# FLEX_TOP_MOSFETS.net
KiCad netlist of a schematic drawn in Altium Designer
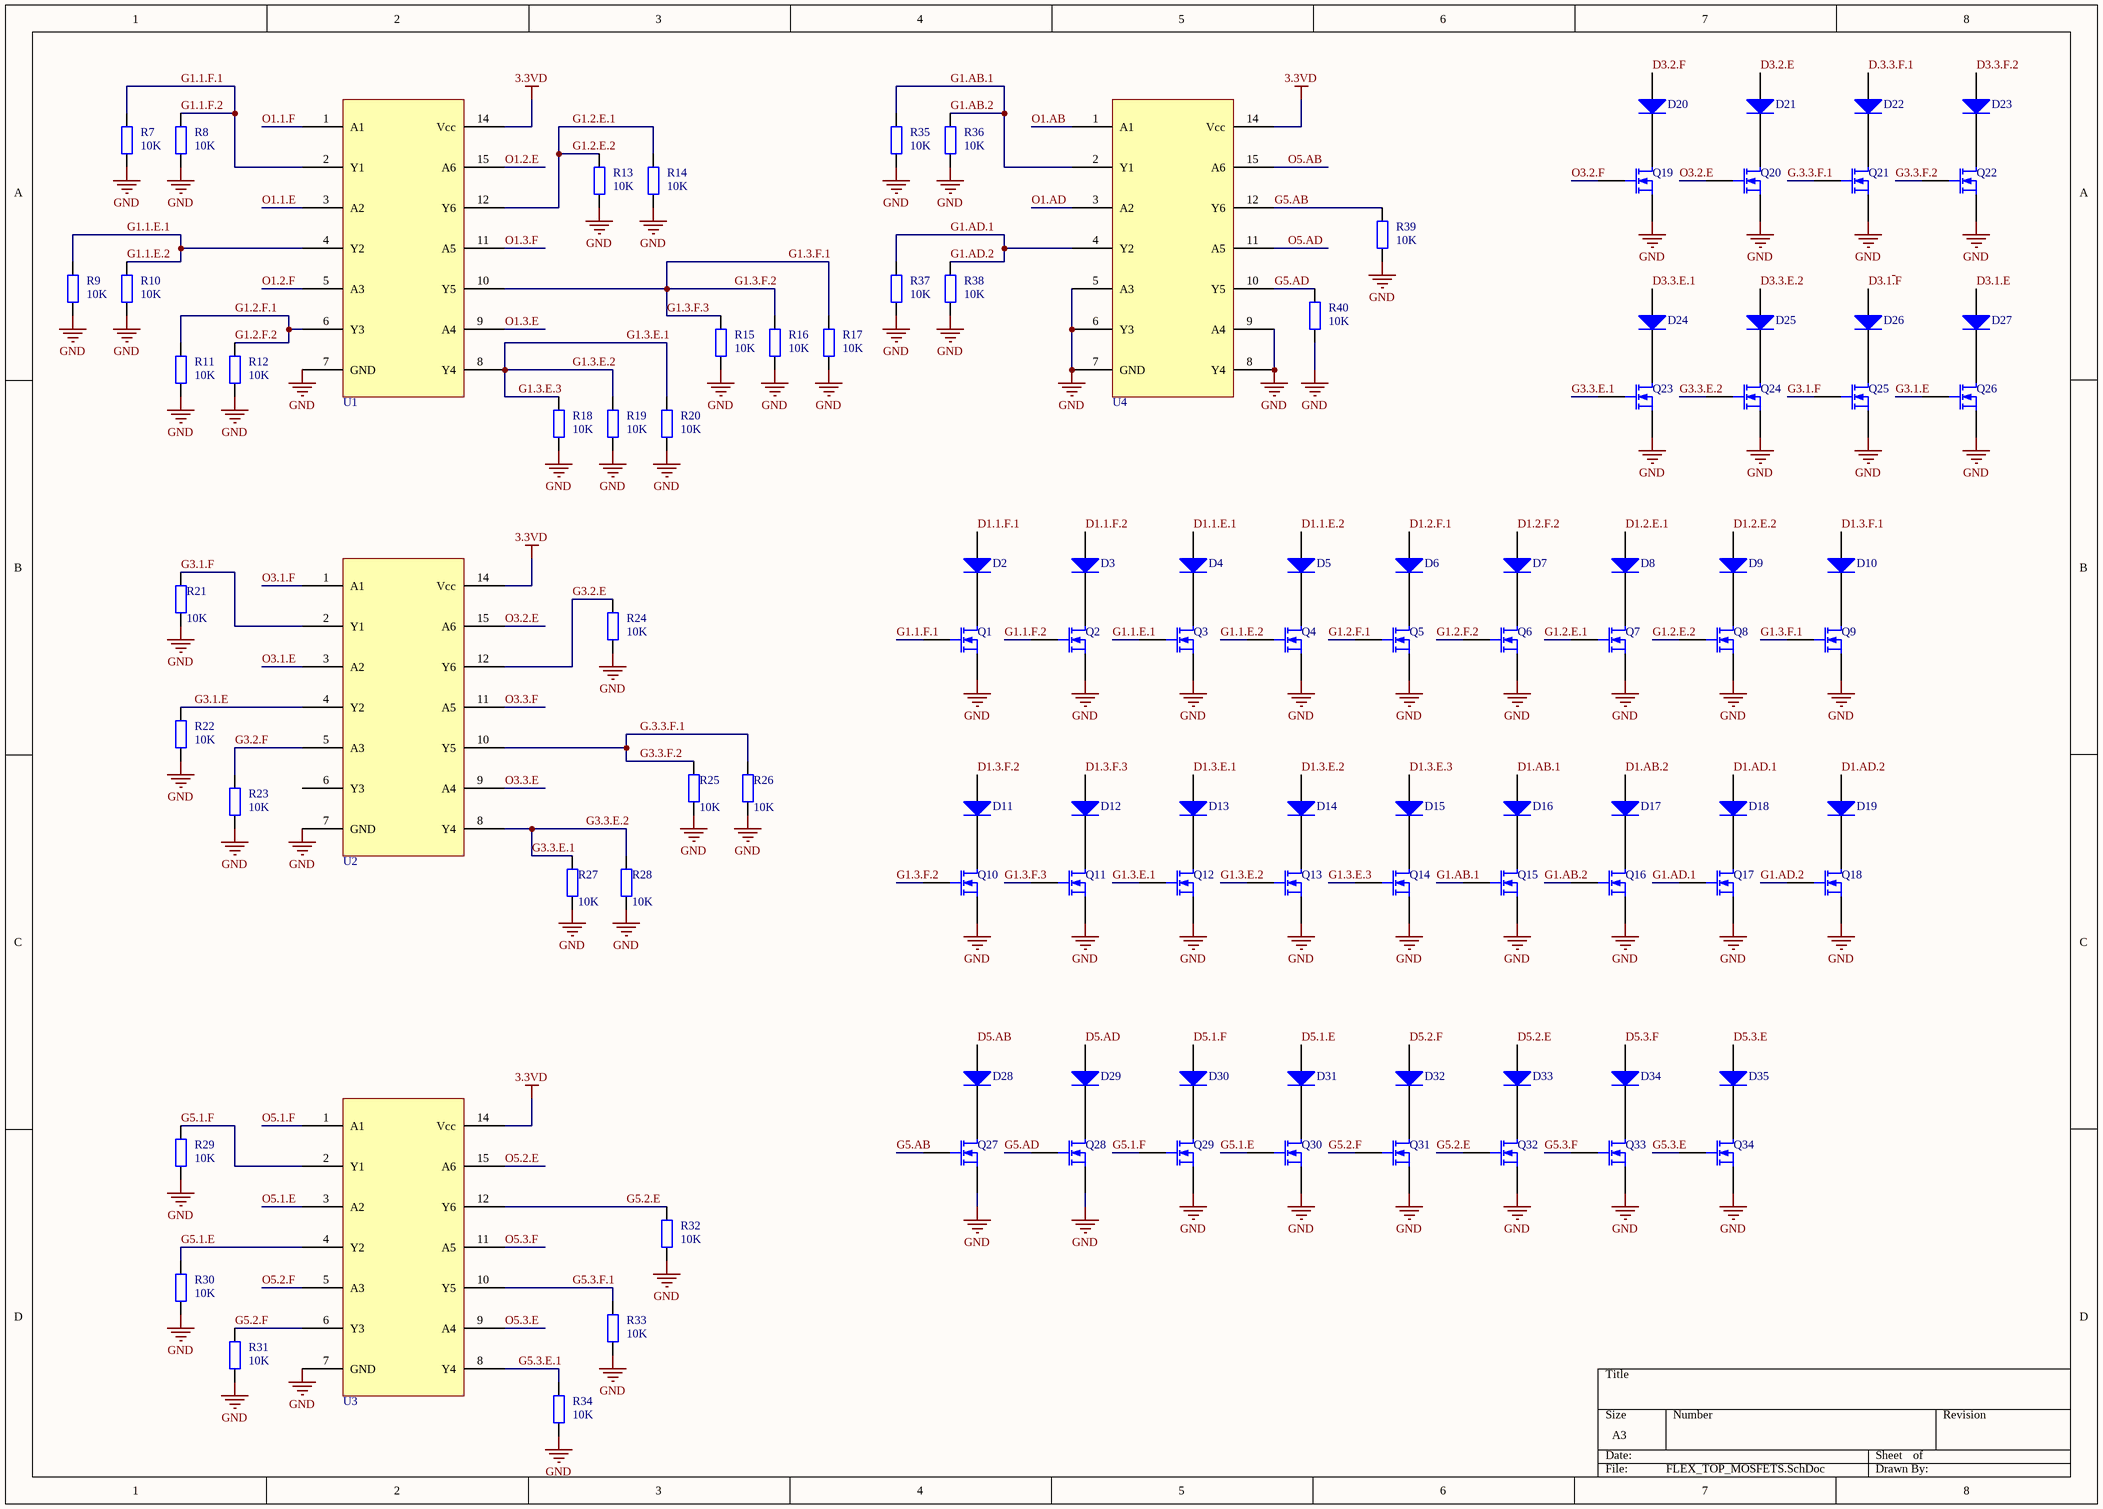
[diagram p0: FLEX_TOP_MOSFETS.SchDoc]

(export (version "E")
  (design (tool "Eeschema 10.0.6"))
  (components
    (comp (ref "D2")
      (value "de")
      (footprint "Diode_Shottky")
      (description "Default Diode")
      (fields (field (name "PUBLISHER") "Altium Limited"))
      (libsource (lib "Miscellaneous Devices") (part "Diode"))
    )
    (comp (ref "D3")
      (value "de")
      (footprint "Diode_Shottky")
      (description "Default Diode")
      (fields (field (name "PUBLISHER") "Altium Limited"))
      (libsource (lib "Miscellaneous Devices") (part "Diode"))
    )
    (comp (ref "D4")
      (value "de")
      (footprint "Diode_Shottky")
      (description "Default Diode")
      (fields (field (name "PUBLISHER") "Altium Limited"))
      (libsource (lib "Miscellaneous Devices") (part "Diode"))
    )
    (comp (ref "D5")
      (value "de")
      (footprint "Diode_Shottky")
      (description "Default Diode")
      (fields (field (name "PUBLISHER") "Altium Limited"))
      (libsource (lib "Miscellaneous Devices") (part "Diode"))
    )
    (comp (ref "D6")
      (value "de")
      (footprint "Diode_Shottky")
      (description "Default Diode")
      (fields (field (name "PUBLISHER") "Altium Limited"))
      (libsource (lib "Miscellaneous Devices") (part "Diode"))
    )
    (comp (ref "D7")
      (value "de")
      (footprint "Diode_Shottky")
      (description "Default Diode")
      (fields (field (name "PUBLISHER") "Altium Limited"))
      (libsource (lib "Miscellaneous Devices") (part "Diode"))
    )
    (comp (ref "D8")
      (value "de")
      (footprint "Diode_Shottky")
      (description "Default Diode")
      (fields (field (name "PUBLISHER") "Altium Limited"))
      (libsource (lib "Miscellaneous Devices") (part "Diode"))
    )
    (comp (ref "D9")
      (value "de")
      (footprint "Diode_Shottky")
      (description "Default Diode")
      (fields (field (name "PUBLISHER") "Altium Limited"))
      (libsource (lib "Miscellaneous Devices") (part "Diode"))
    )
    (comp (ref "D10")
      (value "de")
      (footprint "Diode_Shottky")
      (description "Default Diode")
      (fields (field (name "PUBLISHER") "Altium Limited"))
      (libsource (lib "Miscellaneous Devices") (part "Diode"))
    )
    (comp (ref "D11")
      (value "de")
      (footprint "Diode_Shottky")
      (description "Default Diode")
      (fields (field (name "PUBLISHER") "Altium Limited"))
      (libsource (lib "Miscellaneous Devices") (part "Diode"))
    )
    (comp (ref "D12")
      (value "de")
      (footprint "Diode_Shottky")
      (description "Default Diode")
      (fields (field (name "PUBLISHER") "Altium Limited"))
      (libsource (lib "Miscellaneous Devices") (part "Diode"))
    )
    (comp (ref "D13")
      (value "de")
      (footprint "Diode_Shottky")
      (description "Default Diode")
      (fields (field (name "PUBLISHER") "Altium Limited"))
      (libsource (lib "Miscellaneous Devices") (part "Diode"))
    )
    (comp (ref "D14")
      (value "de")
      (footprint "Diode_Shottky")
      (description "Default Diode")
      (fields (field (name "PUBLISHER") "Altium Limited"))
      (libsource (lib "Miscellaneous Devices") (part "Diode"))
    )
    (comp (ref "D15")
      (value "de")
      (footprint "Diode_Shottky")
      (description "Default Diode")
      (fields (field (name "PUBLISHER") "Altium Limited"))
      (libsource (lib "Miscellaneous Devices") (part "Diode"))
    )
    (comp (ref "D16")
      (value "de")
      (footprint "Diode_Shottky")
      (description "Default Diode")
      (fields (field (name "PUBLISHER") "Altium Limited"))
      (libsource (lib "Miscellaneous Devices") (part "Diode"))
    )
    (comp (ref "D17")
      (value "de")
      (footprint "Diode_Shottky")
      (description "Default Diode")
      (fields (field (name "PUBLISHER") "Altium Limited"))
      (libsource (lib "Miscellaneous Devices") (part "Diode"))
    )
    (comp (ref "D18")
      (value "de")
      (footprint "Diode_Shottky")
      (description "Default Diode")
      (fields (field (name "PUBLISHER") "Altium Limited"))
      (libsource (lib "Miscellaneous Devices") (part "Diode"))
    )
    (comp (ref "D19")
      (value "de")
      (footprint "Diode_Shottky")
      (description "Default Diode")
      (fields (field (name "PUBLISHER") "Altium Limited"))
      (libsource (lib "Miscellaneous Devices") (part "Diode"))
    )
    (comp (ref "D20")
      (value "de")
      (footprint "Diode_Shottky")
      (description "Default Diode")
      (fields (field (name "PUBLISHER") "Altium Limited"))
      (libsource (lib "Miscellaneous Devices") (part "Diode"))
    )
    (comp (ref "D21")
      (value "de")
      (footprint "Diode_Shottky")
      (description "Default Diode")
      (fields (field (name "PUBLISHER") "Altium Limited"))
      (libsource (lib "Miscellaneous Devices") (part "Diode"))
    )
    (comp (ref "D22")
      (value "de")
      (footprint "Diode_Shottky")
      (description "Default Diode")
      (fields (field (name "PUBLISHER") "Altium Limited"))
      (libsource (lib "Miscellaneous Devices") (part "Diode"))
    )
    (comp (ref "D23")
      (value "de")
      (footprint "Diode_Shottky")
      (description "Default Diode")
      (fields (field (name "PUBLISHER") "Altium Limited"))
      (libsource (lib "Miscellaneous Devices") (part "Diode"))
    )
    (comp (ref "D24")
      (value "de")
      (footprint "Diode_Shottky")
      (description "Default Diode")
      (fields (field (name "PUBLISHER") "Altium Limited"))
      (libsource (lib "Miscellaneous Devices") (part "Diode"))
    )
    (comp (ref "D25")
      (value "de")
      (footprint "Diode_Shottky")
      (description "Default Diode")
      (fields (field (name "PUBLISHER") "Altium Limited"))
      (libsource (lib "Miscellaneous Devices") (part "Diode"))
    )
    (comp (ref "D26")
      (value "de")
      (footprint "Diode_Shottky")
      (description "Default Diode")
      (fields (field (name "PUBLISHER") "Altium Limited"))
      (libsource (lib "Miscellaneous Devices") (part "Diode"))
    )
    (comp (ref "D27")
      (value "de")
      (footprint "Diode_Shottky")
      (description "Default Diode")
      (fields (field (name "PUBLISHER") "Altium Limited"))
      (libsource (lib "Miscellaneous Devices") (part "Diode"))
    )
    (comp (ref "D28")
      (value "de")
      (footprint "Diode_Shottky")
      (description "Default Diode")
      (fields (field (name "PUBLISHER") "Altium Limited"))
      (libsource (lib "Miscellaneous Devices") (part "Diode"))
    )
    (comp (ref "D29")
      (value "de")
      (footprint "Diode_Shottky")
      (description "Default Diode")
      (fields (field (name "PUBLISHER") "Altium Limited"))
      (libsource (lib "Miscellaneous Devices") (part "Diode"))
    )
    (comp (ref "D30")
      (value "de")
      (footprint "Diode_Shottky")
      (description "Default Diode")
      (fields (field (name "PUBLISHER") "Altium Limited"))
      (libsource (lib "Miscellaneous Devices") (part "Diode"))
    )
    (comp (ref "D31")
      (value "de")
      (footprint "Diode_Shottky")
      (description "Default Diode")
      (fields (field (name "PUBLISHER") "Altium Limited"))
      (libsource (lib "Miscellaneous Devices") (part "Diode"))
    )
    (comp (ref "D32")
      (value "de")
      (footprint "Diode_Shottky")
      (description "Default Diode")
      (fields (field (name "PUBLISHER") "Altium Limited"))
      (libsource (lib "Miscellaneous Devices") (part "Diode"))
    )
    (comp (ref "D33")
      (value "de")
      (footprint "Diode_Shottky")
      (description "Default Diode")
      (fields (field (name "PUBLISHER") "Altium Limited"))
      (libsource (lib "Miscellaneous Devices") (part "Diode"))
    )
    (comp (ref "D34")
      (value "de")
      (footprint "Diode_Shottky")
      (description "Default Diode")
      (fields (field (name "PUBLISHER") "Altium Limited"))
      (libsource (lib "Miscellaneous Devices") (part "Diode"))
    )
    (comp (ref "D35")
      (value "de")
      (footprint "Diode_Shottky")
      (description "Default Diode")
      (fields (field (name "PUBLISHER") "Altium Limited"))
      (libsource (lib "Miscellaneous Devices") (part "Diode"))
    )
    (comp (ref "Q1")
      (value "~")
      (footprint "MOSFET")
      (description "N-Channel MOSFET")
      (fields (field (name "PUBLISHER") "Altium Limited"))
      (libsource (lib "Miscellaneous Devices") (part "MOSFET-N"))
    )
    (comp (ref "Q2")
      (value "~")
      (footprint "MOSFET")
      (description "N-Channel MOSFET")
      (fields (field (name "PUBLISHER") "Altium Limited"))
      (libsource (lib "Miscellaneous Devices") (part "MOSFET-N"))
    )
    (comp (ref "Q3")
      (value "~")
      (footprint "MOSFET")
      (description "N-Channel MOSFET")
      (fields (field (name "PUBLISHER") "Altium Limited"))
      (libsource (lib "Miscellaneous Devices") (part "MOSFET-N"))
    )
    (comp (ref "Q4")
      (value "~")
      (footprint "MOSFET")
      (description "N-Channel MOSFET")
      (fields (field (name "PUBLISHER") "Altium Limited"))
      (libsource (lib "Miscellaneous Devices") (part "MOSFET-N"))
    )
    (comp (ref "Q5")
      (value "~")
      (footprint "MOSFET")
      (description "N-Channel MOSFET")
      (fields (field (name "PUBLISHER") "Altium Limited"))
      (libsource (lib "Miscellaneous Devices") (part "MOSFET-N"))
    )
    (comp (ref "Q6")
      (value "~")
      (footprint "MOSFET")
      (description "N-Channel MOSFET")
      (fields (field (name "PUBLISHER") "Altium Limited"))
      (libsource (lib "Miscellaneous Devices") (part "MOSFET-N"))
    )
    (comp (ref "Q7")
      (value "~")
      (footprint "MOSFET")
      (description "N-Channel MOSFET")
      (fields (field (name "PUBLISHER") "Altium Limited"))
      (libsource (lib "Miscellaneous Devices") (part "MOSFET-N"))
    )
    (comp (ref "Q8")
      (value "~")
      (footprint "MOSFET")
      (description "N-Channel MOSFET")
      (fields (field (name "PUBLISHER") "Altium Limited"))
      (libsource (lib "Miscellaneous Devices") (part "MOSFET-N"))
    )
    (comp (ref "Q9")
      (value "~")
      (footprint "MOSFET")
      (description "N-Channel MOSFET")
      (fields (field (name "PUBLISHER") "Altium Limited"))
      (libsource (lib "Miscellaneous Devices") (part "MOSFET-N"))
    )
    (comp (ref "Q10")
      (value "~")
      (footprint "MOSFET")
      (description "N-Channel MOSFET")
      (fields (field (name "PUBLISHER") "Altium Limited"))
      (libsource (lib "Miscellaneous Devices") (part "MOSFET-N"))
    )
    (comp (ref "Q11")
      (value "~")
      (footprint "MOSFET")
      (description "N-Channel MOSFET")
      (fields (field (name "PUBLISHER") "Altium Limited"))
      (libsource (lib "Miscellaneous Devices") (part "MOSFET-N"))
    )
    (comp (ref "Q12")
      (value "~")
      (footprint "MOSFET")
      (description "N-Channel MOSFET")
      (fields (field (name "PUBLISHER") "Altium Limited"))
      (libsource (lib "Miscellaneous Devices") (part "MOSFET-N"))
    )
    (comp (ref "Q13")
      (value "~")
      (footprint "MOSFET")
      (description "N-Channel MOSFET")
      (fields (field (name "PUBLISHER") "Altium Limited"))
      (libsource (lib "Miscellaneous Devices") (part "MOSFET-N"))
    )
    (comp (ref "Q14")
      (value "~")
      (footprint "MOSFET")
      (description "N-Channel MOSFET")
      (fields (field (name "PUBLISHER") "Altium Limited"))
      (libsource (lib "Miscellaneous Devices") (part "MOSFET-N"))
    )
    (comp (ref "Q15")
      (value "~")
      (footprint "MOSFET")
      (description "N-Channel MOSFET")
      (fields (field (name "PUBLISHER") "Altium Limited"))
      (libsource (lib "Miscellaneous Devices") (part "MOSFET-N"))
    )
    (comp (ref "Q16")
      (value "~")
      (footprint "MOSFET")
      (description "N-Channel MOSFET")
      (fields (field (name "PUBLISHER") "Altium Limited"))
      (libsource (lib "Miscellaneous Devices") (part "MOSFET-N"))
    )
    (comp (ref "Q17")
      (value "~")
      (footprint "MOSFET")
      (description "N-Channel MOSFET")
      (fields (field (name "PUBLISHER") "Altium Limited"))
      (libsource (lib "Miscellaneous Devices") (part "MOSFET-N"))
    )
    (comp (ref "Q18")
      (value "~")
      (footprint "MOSFET")
      (description "N-Channel MOSFET")
      (fields (field (name "PUBLISHER") "Altium Limited"))
      (libsource (lib "Miscellaneous Devices") (part "MOSFET-N"))
    )
    (comp (ref "Q19")
      (value "~")
      (footprint "MOSFET")
      (description "N-Channel MOSFET")
      (fields (field (name "PUBLISHER") "Altium Limited"))
      (libsource (lib "Miscellaneous Devices") (part "MOSFET-N"))
    )
    (comp (ref "Q20")
      (value "~")
      (footprint "MOSFET")
      (description "N-Channel MOSFET")
      (fields (field (name "PUBLISHER") "Altium Limited"))
      (libsource (lib "Miscellaneous Devices") (part "MOSFET-N"))
    )
    (comp (ref "Q21")
      (value "~")
      (footprint "MOSFET")
      (description "N-Channel MOSFET")
      (fields (field (name "PUBLISHER") "Altium Limited"))
      (libsource (lib "Miscellaneous Devices") (part "MOSFET-N"))
    )
    (comp (ref "Q22")
      (value "~")
      (footprint "MOSFET")
      (description "N-Channel MOSFET")
      (fields (field (name "PUBLISHER") "Altium Limited"))
      (libsource (lib "Miscellaneous Devices") (part "MOSFET-N"))
    )
    (comp (ref "Q23")
      (value "~")
      (footprint "MOSFET")
      (description "N-Channel MOSFET")
      (fields (field (name "PUBLISHER") "Altium Limited"))
      (libsource (lib "Miscellaneous Devices") (part "MOSFET-N"))
    )
    (comp (ref "Q24")
      (value "~")
      (footprint "MOSFET")
      (description "N-Channel MOSFET")
      (fields (field (name "PUBLISHER") "Altium Limited"))
      (libsource (lib "Miscellaneous Devices") (part "MOSFET-N"))
    )
    (comp (ref "Q25")
      (value "~")
      (footprint "MOSFET")
      (description "N-Channel MOSFET")
      (fields (field (name "PUBLISHER") "Altium Limited"))
      (libsource (lib "Miscellaneous Devices") (part "MOSFET-N"))
    )
    (comp (ref "Q26")
      (value "~")
      (footprint "MOSFET")
      (description "N-Channel MOSFET")
      (fields (field (name "PUBLISHER") "Altium Limited"))
      (libsource (lib "Miscellaneous Devices") (part "MOSFET-N"))
    )
    (comp (ref "Q27")
      (value "~")
      (footprint "MOSFET")
      (description "N-Channel MOSFET")
      (fields (field (name "PUBLISHER") "Altium Limited"))
      (libsource (lib "Miscellaneous Devices") (part "MOSFET-N"))
    )
    (comp (ref "Q28")
      (value "~")
      (footprint "MOSFET")
      (description "N-Channel MOSFET")
      (fields (field (name "PUBLISHER") "Altium Limited"))
      (libsource (lib "Miscellaneous Devices") (part "MOSFET-N"))
    )
    (comp (ref "Q29")
      (value "~")
      (footprint "MOSFET")
      (description "N-Channel MOSFET")
      (fields (field (name "PUBLISHER") "Altium Limited"))
      (libsource (lib "Miscellaneous Devices") (part "MOSFET-N"))
    )
    (comp (ref "Q30")
      (value "~")
      (footprint "MOSFET")
      (description "N-Channel MOSFET")
      (fields (field (name "PUBLISHER") "Altium Limited"))
      (libsource (lib "Miscellaneous Devices") (part "MOSFET-N"))
    )
    (comp (ref "Q31")
      (value "~")
      (footprint "MOSFET")
      (description "N-Channel MOSFET")
      (fields (field (name "PUBLISHER") "Altium Limited"))
      (libsource (lib "Miscellaneous Devices") (part "MOSFET-N"))
    )
    (comp (ref "Q32")
      (value "~")
      (footprint "MOSFET")
      (description "N-Channel MOSFET")
      (fields (field (name "PUBLISHER") "Altium Limited"))
      (libsource (lib "Miscellaneous Devices") (part "MOSFET-N"))
    )
    (comp (ref "Q33")
      (value "~")
      (footprint "MOSFET")
      (description "N-Channel MOSFET")
      (fields (field (name "PUBLISHER") "Altium Limited"))
      (libsource (lib "Miscellaneous Devices") (part "MOSFET-N"))
    )
    (comp (ref "Q34")
      (value "~")
      (footprint "MOSFET")
      (description "N-Channel MOSFET")
      (fields (field (name "PUBLISHER") "Altium Limited"))
      (libsource (lib "Miscellaneous Devices") (part "MOSFET-N"))
    )
    (comp (ref "R7")
      (value "10K")
      (footprint "Panasonic ERJ-Series (1608)")
      (description "Resistor")
      (fields (field (name "PUBLISHER") "Altium Limited"))
      (libsource (lib "Miscellaneous Devices") (part "Res2"))
    )
    (comp (ref "R8")
      (value "10K")
      (footprint "Panasonic ERJ-Series (1608)")
      (description "Resistor")
      (fields (field (name "PUBLISHER") "Altium Limited"))
      (libsource (lib "Miscellaneous Devices") (part "Res2"))
    )
    (comp (ref "R9")
      (value "10K")
      (footprint "Panasonic ERJ-Series (1608)")
      (description "Resistor")
      (fields (field (name "PUBLISHER") "Altium Limited"))
      (libsource (lib "Miscellaneous Devices") (part "Res2"))
    )
    (comp (ref "R10")
      (value "10K")
      (footprint "Panasonic ERJ-Series (1608)")
      (description "Resistor")
      (fields (field (name "PUBLISHER") "Altium Limited"))
      (libsource (lib "Miscellaneous Devices") (part "Res2"))
    )
    (comp (ref "R11")
      (value "10K")
      (footprint "Panasonic ERJ-Series (1608)")
      (description "Resistor")
      (fields (field (name "PUBLISHER") "Altium Limited"))
      (libsource (lib "Miscellaneous Devices") (part "Res2"))
    )
    (comp (ref "R12")
      (value "10K")
      (footprint "Panasonic ERJ-Series (1608)")
      (description "Resistor")
      (fields (field (name "PUBLISHER") "Altium Limited"))
      (libsource (lib "Miscellaneous Devices") (part "Res2"))
    )
    (comp (ref "R13")
      (value "10K")
      (footprint "Panasonic ERJ-Series (1608)")
      (description "Resistor")
      (fields (field (name "PUBLISHER") "Altium Limited"))
      (libsource (lib "Miscellaneous Devices") (part "Res2"))
    )
    (comp (ref "R14")
      (value "10K")
      (footprint "Panasonic ERJ-Series (1608)")
      (description "Resistor")
      (fields (field (name "PUBLISHER") "Altium Limited"))
      (libsource (lib "Miscellaneous Devices") (part "Res2"))
    )
    (comp (ref "R15")
      (value "10K")
      (footprint "Panasonic ERJ-Series (1608)")
      (description "Resistor")
      (fields (field (name "PUBLISHER") "Altium Limited"))
      (libsource (lib "Miscellaneous Devices") (part "Res2"))
    )
    (comp (ref "R16")
      (value "10K")
      (footprint "Panasonic ERJ-Series (1608)")
      (description "Resistor")
      (fields (field (name "PUBLISHER") "Altium Limited"))
      (libsource (lib "Miscellaneous Devices") (part "Res2"))
    )
    (comp (ref "R17")
      (value "10K")
      (footprint "Panasonic ERJ-Series (1608)")
      (description "Resistor")
      (fields (field (name "PUBLISHER") "Altium Limited"))
      (libsource (lib "Miscellaneous Devices") (part "Res2"))
    )
    (comp (ref "R18")
      (value "10K")
      (footprint "Panasonic ERJ-Series (1608)")
      (description "Resistor")
      (fields (field (name "PUBLISHER") "Altium Limited"))
      (libsource (lib "Miscellaneous Devices") (part "Res2"))
    )
    (comp (ref "R19")
      (value "10K")
      (footprint "Panasonic ERJ-Series (1608)")
      (description "Resistor")
      (fields (field (name "PUBLISHER") "Altium Limited"))
      (libsource (lib "Miscellaneous Devices") (part "Res2"))
    )
    (comp (ref "R20")
      (value "10K")
      (footprint "Panasonic ERJ-Series (1608)")
      (description "Resistor")
      (fields (field (name "PUBLISHER") "Altium Limited"))
      (libsource (lib "Miscellaneous Devices") (part "Res2"))
    )
    (comp (ref "R21")
      (value "10K")
      (footprint "Panasonic ERJ-Series (1608)")
      (description "Resistor")
      (fields (field (name "PUBLISHER") "Altium Limited"))
      (libsource (lib "Miscellaneous Devices") (part "Res2"))
    )
    (comp (ref "R22")
      (value "10K")
      (footprint "Panasonic ERJ-Series (1608)")
      (description "Resistor")
      (fields (field (name "PUBLISHER") "Altium Limited"))
      (libsource (lib "Miscellaneous Devices") (part "Res2"))
    )
    (comp (ref "R23")
      (value "10K")
      (footprint "Panasonic ERJ-Series (1608)")
      (description "Resistor")
      (fields (field (name "PUBLISHER") "Altium Limited"))
      (libsource (lib "Miscellaneous Devices") (part "Res2"))
    )
    (comp (ref "R24")
      (value "10K")
      (footprint "Panasonic ERJ-Series (1608)")
      (description "Resistor")
      (fields (field (name "PUBLISHER") "Altium Limited"))
      (libsource (lib "Miscellaneous Devices") (part "Res2"))
    )
    (comp (ref "R25")
      (value "10K")
      (footprint "Panasonic ERJ-Series (1608)")
      (description "Resistor")
      (fields (field (name "PUBLISHER") "Altium Limited"))
      (libsource (lib "Miscellaneous Devices") (part "Res2"))
    )
    (comp (ref "R26")
      (value "10K")
      (footprint "Panasonic ERJ-Series (1608)")
      (description "Resistor")
      (fields (field (name "PUBLISHER") "Altium Limited"))
      (libsource (lib "Miscellaneous Devices") (part "Res2"))
    )
    (comp (ref "R27")
      (value "10K")
      (footprint "Panasonic ERJ-Series (1608)")
      (description "Resistor")
      (fields (field (name "PUBLISHER") "Altium Limited"))
      (libsource (lib "Miscellaneous Devices") (part "Res2"))
    )
    (comp (ref "R28")
      (value "10K")
      (footprint "Panasonic ERJ-Series (1608)")
      (description "Resistor")
      (fields (field (name "PUBLISHER") "Altium Limited"))
      (libsource (lib "Miscellaneous Devices") (part "Res2"))
    )
    (comp (ref "R29")
      (value "10K")
      (footprint "Panasonic ERJ-Series (1608)")
      (description "Resistor")
      (fields (field (name "PUBLISHER") "Altium Limited"))
      (libsource (lib "Miscellaneous Devices") (part "Res2"))
    )
    (comp (ref "R30")
      (value "10K")
      (footprint "Panasonic ERJ-Series (1608)")
      (description "Resistor")
      (fields (field (name "PUBLISHER") "Altium Limited"))
      (libsource (lib "Miscellaneous Devices") (part "Res2"))
    )
    (comp (ref "R31")
      (value "10K")
      (footprint "Panasonic ERJ-Series (1608)")
      (description "Resistor")
      (fields (field (name "PUBLISHER") "Altium Limited"))
      (libsource (lib "Miscellaneous Devices") (part "Res2"))
    )
    (comp (ref "R32")
      (value "10K")
      (footprint "Panasonic ERJ-Series (1608)")
      (description "Resistor")
      (fields (field (name "PUBLISHER") "Altium Limited"))
      (libsource (lib "Miscellaneous Devices") (part "Res2"))
    )
    (comp (ref "R33")
      (value "10K")
      (footprint "Panasonic ERJ-Series (1608)")
      (description "Resistor")
      (fields (field (name "PUBLISHER") "Altium Limited"))
      (libsource (lib "Miscellaneous Devices") (part "Res2"))
    )
    (comp (ref "R34")
      (value "10K")
      (footprint "Panasonic ERJ-Series (1608)")
      (description "Resistor")
      (fields (field (name "PUBLISHER") "Altium Limited"))
      (libsource (lib "Miscellaneous Devices") (part "Res2"))
    )
    (comp (ref "R35")
      (value "10K")
      (footprint "Panasonic ERJ-Series (1608)")
      (description "Resistor")
      (fields (field (name "PUBLISHER") "Altium Limited"))
      (libsource (lib "Miscellaneous Devices") (part "Res2"))
    )
    (comp (ref "R36")
      (value "10K")
      (footprint "Panasonic ERJ-Series (1608)")
      (description "Resistor")
      (fields (field (name "PUBLISHER") "Altium Limited"))
      (libsource (lib "Miscellaneous Devices") (part "Res2"))
    )
    (comp (ref "R37")
      (value "10K")
      (footprint "Panasonic ERJ-Series (1608)")
      (description "Resistor")
      (fields (field (name "PUBLISHER") "Altium Limited"))
      (libsource (lib "Miscellaneous Devices") (part "Res2"))
    )
    (comp (ref "R38")
      (value "10K")
      (footprint "Panasonic ERJ-Series (1608)")
      (description "Resistor")
      (fields (field (name "PUBLISHER") "Altium Limited"))
      (libsource (lib "Miscellaneous Devices") (part "Res2"))
    )
    (comp (ref "R39")
      (value "10K")
      (footprint "Panasonic ERJ-Series (1608)")
      (description "Resistor")
      (fields (field (name "PUBLISHER") "Altium Limited"))
      (libsource (lib "Miscellaneous Devices") (part "Res2"))
    )
    (comp (ref "R40")
      (value "10K")
      (footprint "Panasonic ERJ-Series (1608)")
      (description "Resistor")
      (fields (field (name "PUBLISHER") "Altium Limited"))
      (libsource (lib "Miscellaneous Devices") (part "Res2"))
    )
    (comp (ref "U1")
      (value "MC74VHCT50A")
      (description "6-Channel CMOS Buffer")
      (libsource (lib "Schematics Library") (part "MC74VHCT50A"))
    )
    (comp (ref "U2")
      (value "MC74VHCT50A")
      (description "6-Channel CMOS Buffer")
      (libsource (lib "Schematics Library") (part "MC74VHCT50A"))
    )
    (comp (ref "U3")
      (value "MC74VHCT50A")
      (description "6-Channel CMOS Buffer")
      (libsource (lib "Schematics Library") (part "MC74VHCT50A"))
    )
    (comp (ref "U4")
      (value "MC74VHCT50A")
      (description "6-Channel CMOS Buffer")
      (libsource (lib "Schematics Library") (part "MC74VHCT50A"))
    )
  )
  (nets
    (net (code "1") (name "/D.3.3.F.1") (class "Default")
      (node (ref "D22") (pin "1") (pinfunction "A_1") (pintype "passive"))
    )
    (net (code "2") (name "/D1.1.E.1") (class "Default")
      (node (ref "D4") (pin "1") (pinfunction "A_1") (pintype "passive"))
    )
    (net (code "3") (name "/D1.1.E.2") (class "Default")
      (node (ref "D5") (pin "1") (pinfunction "A_1") (pintype "passive"))
    )
    (net (code "4") (name "/D1.1.F.1") (class "Default")
      (node (ref "D2") (pin "1") (pinfunction "A_1") (pintype "passive"))
    )
    (net (code "5") (name "/D1.1.F.2") (class "Default")
      (node (ref "D3") (pin "1") (pinfunction "A_1") (pintype "passive"))
    )
    (net (code "6") (name "/D1.2.E.1") (class "Default")
      (node (ref "D8") (pin "1") (pinfunction "A_1") (pintype "passive"))
    )
    (net (code "7") (name "/D1.2.E.2") (class "Default")
      (node (ref "D9") (pin "1") (pinfunction "A_1") (pintype "passive"))
    )
    (net (code "8") (name "/D1.2.F.1") (class "Default")
      (node (ref "D6") (pin "1") (pinfunction "A_1") (pintype "passive"))
    )
    (net (code "9") (name "/D1.2.F.2") (class "Default")
      (node (ref "D7") (pin "1") (pinfunction "A_1") (pintype "passive"))
    )
    (net (code "10") (name "/D1.3.E.1") (class "Default")
      (node (ref "D13") (pin "1") (pinfunction "A_1") (pintype "passive"))
    )
    (net (code "11") (name "/D1.3.E.2") (class "Default")
      (node (ref "D14") (pin "1") (pinfunction "A_1") (pintype "passive"))
    )
    (net (code "12") (name "/D1.3.E.3") (class "Default")
      (node (ref "D15") (pin "1") (pinfunction "A_1") (pintype "passive"))
    )
    (net (code "13") (name "/D1.3.F.1") (class "Default")
      (node (ref "D10") (pin "1") (pinfunction "A_1") (pintype "passive"))
    )
    (net (code "14") (name "/D1.3.F.2") (class "Default")
      (node (ref "D11") (pin "1") (pinfunction "A_1") (pintype "passive"))
    )
    (net (code "15") (name "/D1.3.F.3") (class "Default")
      (node (ref "D12") (pin "1") (pinfunction "A_1") (pintype "passive"))
    )
    (net (code "16") (name "/D1.AB.1") (class "Default")
      (node (ref "D16") (pin "1") (pinfunction "A_1") (pintype "passive"))
    )
    (net (code "17") (name "/D1.AB.2") (class "Default")
      (node (ref "D17") (pin "1") (pinfunction "A_1") (pintype "passive"))
    )
    (net (code "18") (name "/D1.AD.1") (class "Default")
      (node (ref "D18") (pin "1") (pinfunction "A_1") (pintype "passive"))
    )
    (net (code "19") (name "/D1.AD.2") (class "Default")
      (node (ref "D19") (pin "1") (pinfunction "A_1") (pintype "passive"))
    )
    (net (code "20") (name "/D3.1.E") (class "Default")
      (node (ref "D27") (pin "1") (pinfunction "A_1") (pintype "passive"))
    )
    (net (code "21") (name "/D3.1~{.}F") (class "Default")
      (node (ref "D26") (pin "1") (pinfunction "A_1") (pintype "passive"))
    )
    (net (code "22") (name "/D3.2.E") (class "Default")
      (node (ref "D21") (pin "1") (pinfunction "A_1") (pintype "passive"))
    )
    (net (code "23") (name "/D3.2.F") (class "Default")
      (node (ref "D20") (pin "1") (pinfunction "A_1") (pintype "passive"))
    )
    (net (code "24") (name "/D3.3.E.1") (class "Default")
      (node (ref "D24") (pin "1") (pinfunction "A_1") (pintype "passive"))
    )
    (net (code "25") (name "/D3.3.E.2") (class "Default")
      (node (ref "D25") (pin "1") (pinfunction "A_1") (pintype "passive"))
    )
    (net (code "26") (name "/D3.3.F.2") (class "Default")
      (node (ref "D23") (pin "1") (pinfunction "A_1") (pintype "passive"))
    )
    (net (code "27") (name "/D5.1.E") (class "Default")
      (node (ref "D31") (pin "1") (pinfunction "A_1") (pintype "passive"))
    )
    (net (code "28") (name "/D5.1.F") (class "Default")
      (node (ref "D30") (pin "1") (pinfunction "A_1") (pintype "passive"))
    )
    (net (code "29") (name "/D5.2.E") (class "Default")
      (node (ref "D33") (pin "1") (pinfunction "A_1") (pintype "passive"))
    )
    (net (code "30") (name "/D5.2.F") (class "Default")
      (node (ref "D32") (pin "1") (pinfunction "A_1") (pintype "passive"))
    )
    (net (code "31") (name "/D5.3.E") (class "Default")
      (node (ref "D35") (pin "1") (pinfunction "A_1") (pintype "passive"))
    )
    (net (code "32") (name "/D5.3.F") (class "Default")
      (node (ref "D34") (pin "1") (pinfunction "A_1") (pintype "passive"))
    )
    (net (code "33") (name "/D5.AB") (class "Default")
      (node (ref "D28") (pin "1") (pinfunction "A_1") (pintype "passive"))
    )
    (net (code "34") (name "/D5.AD") (class "Default")
      (node (ref "D29") (pin "1") (pinfunction "A_1") (pintype "passive"))
    )
    (net (code "35") (name "/G.3.3.F.1") (class "Default")
      (node (ref "Q21") (pin "2") (pinfunction "G_2") (pintype "passive"))
      (node (ref "Q22") (pin "2") (pinfunction "G_2") (pintype "passive"))
      (node (ref "R25") (pin "2") (pinfunction "2_2") (pintype "passive"))
      (node (ref "R26") (pin "2") (pinfunction "2_2") (pintype "passive"))
      (node (ref "U2") (pin "10") (pinfunction "Y5_10") (pintype "power_in"))
    )
    (net (code "36") (name "/G1.1.E.1") (class "Default")
      (node (ref "Q3") (pin "2") (pinfunction "G_2") (pintype "passive"))
      (node (ref "Q4") (pin "2") (pinfunction "G_2") (pintype "passive"))
      (node (ref "R10") (pin "2") (pinfunction "2_2") (pintype "passive"))
      (node (ref "R9") (pin "2") (pinfunction "2_2") (pintype "passive"))
      (node (ref "U1") (pin "4") (pinfunction "Y2_4") (pintype "power_in"))
    )
    (net (code "37") (name "/G1.1.F.1") (class "Default")
      (node (ref "Q1") (pin "2") (pinfunction "G_2") (pintype "passive"))
      (node (ref "Q2") (pin "2") (pinfunction "G_2") (pintype "passive"))
      (node (ref "R7") (pin "2") (pinfunction "2_2") (pintype "passive"))
      (node (ref "R8") (pin "2") (pinfunction "2_2") (pintype "passive"))
      (node (ref "U1") (pin "2") (pinfunction "Y1_2") (pintype "power_in"))
    )
    (net (code "38") (name "/G1.2.E.1") (class "Default")
      (node (ref "Q7") (pin "2") (pinfunction "G_2") (pintype "passive"))
      (node (ref "Q8") (pin "2") (pinfunction "G_2") (pintype "passive"))
      (node (ref "R13") (pin "2") (pinfunction "2_2") (pintype "passive"))
      (node (ref "R14") (pin "2") (pinfunction "2_2") (pintype "passive"))
      (node (ref "U1") (pin "12") (pinfunction "Y6_12") (pintype "power_in"))
    )
    (net (code "39") (name "/G1.2.F.1") (class "Default")
      (node (ref "Q5") (pin "2") (pinfunction "G_2") (pintype "passive"))
      (node (ref "Q6") (pin "2") (pinfunction "G_2") (pintype "passive"))
      (node (ref "R11") (pin "2") (pinfunction "2_2") (pintype "passive"))
      (node (ref "R12") (pin "2") (pinfunction "2_2") (pintype "passive"))
      (node (ref "U1") (pin "6") (pinfunction "Y3_6") (pintype "power_in"))
    )
    (net (code "40") (name "/G1.3.E.1") (class "Default")
      (node (ref "Q12") (pin "2") (pinfunction "G_2") (pintype "passive"))
      (node (ref "Q13") (pin "2") (pinfunction "G_2") (pintype "passive"))
      (node (ref "Q14") (pin "2") (pinfunction "G_2") (pintype "passive"))
      (node (ref "R18") (pin "2") (pinfunction "2_2") (pintype "passive"))
      (node (ref "R19") (pin "2") (pinfunction "2_2") (pintype "passive"))
      (node (ref "R20") (pin "2") (pinfunction "2_2") (pintype "passive"))
      (node (ref "U1") (pin "8") (pinfunction "Y4_8") (pintype "power_in"))
    )
    (net (code "41") (name "/G1.3.F.1") (class "Default")
      (node (ref "Q10") (pin "2") (pinfunction "G_2") (pintype "passive"))
      (node (ref "Q11") (pin "2") (pinfunction "G_2") (pintype "passive"))
      (node (ref "Q9") (pin "2") (pinfunction "G_2") (pintype "passive"))
      (node (ref "R15") (pin "2") (pinfunction "2_2") (pintype "passive"))
      (node (ref "R16") (pin "2") (pinfunction "2_2") (pintype "passive"))
      (node (ref "R17") (pin "2") (pinfunction "2_2") (pintype "passive"))
      (node (ref "U1") (pin "10") (pinfunction "Y5_10") (pintype "power_in"))
    )
    (net (code "42") (name "/G1.AB.1") (class "Default")
      (node (ref "Q15") (pin "2") (pinfunction "G_2") (pintype "passive"))
      (node (ref "Q16") (pin "2") (pinfunction "G_2") (pintype "passive"))
      (node (ref "R35") (pin "2") (pinfunction "2_2") (pintype "passive"))
      (node (ref "R36") (pin "2") (pinfunction "2_2") (pintype "passive"))
      (node (ref "U4") (pin "2") (pinfunction "Y1_2") (pintype "power_in"))
    )
    (net (code "43") (name "/G1.AD.1") (class "Default")
      (node (ref "Q17") (pin "2") (pinfunction "G_2") (pintype "passive"))
      (node (ref "Q18") (pin "2") (pinfunction "G_2") (pintype "passive"))
      (node (ref "R37") (pin "2") (pinfunction "2_2") (pintype "passive"))
      (node (ref "R38") (pin "2") (pinfunction "2_2") (pintype "passive"))
      (node (ref "U4") (pin "4") (pinfunction "Y2_4") (pintype "power_in"))
    )
    (net (code "44") (name "/G3.1.E") (class "Default")
      (node (ref "Q26") (pin "2") (pinfunction "G_2") (pintype "passive"))
      (node (ref "R22") (pin "2") (pinfunction "2_2") (pintype "passive"))
      (node (ref "U2") (pin "4") (pinfunction "Y2_4") (pintype "power_in"))
    )
    (net (code "45") (name "/G3.1.F") (class "Default")
      (node (ref "Q25") (pin "2") (pinfunction "G_2") (pintype "passive"))
      (node (ref "R21") (pin "2") (pinfunction "2_2") (pintype "passive"))
      (node (ref "U2") (pin "2") (pinfunction "Y1_2") (pintype "power_in"))
    )
    (net (code "46") (name "/G3.2.E") (class "Default")
      (node (ref "R24") (pin "2") (pinfunction "2_2") (pintype "passive"))
      (node (ref "U2") (pin "12") (pinfunction "Y6_12") (pintype "power_in"))
    )
    (net (code "47") (name "/G3.2.F") (class "Default")
      (node (ref "R23") (pin "2") (pinfunction "2_2") (pintype "passive"))
      (node (ref "U2") (pin "5") (pinfunction "A3_5") (pintype "power_in"))
    )
    (net (code "48") (name "/G3.3.E.1") (class "Default")
      (node (ref "Q23") (pin "2") (pinfunction "G_2") (pintype "passive"))
      (node (ref "Q24") (pin "2") (pinfunction "G_2") (pintype "passive"))
      (node (ref "R27") (pin "2") (pinfunction "2_2") (pintype "passive"))
      (node (ref "R28") (pin "2") (pinfunction "2_2") (pintype "passive"))
      (node (ref "U2") (pin "8") (pinfunction "Y4_8") (pintype "power_in"))
    )
    (net (code "49") (name "/G5.1.E") (class "Default")
      (node (ref "Q30") (pin "2") (pinfunction "G_2") (pintype "passive"))
      (node (ref "R30") (pin "2") (pinfunction "2_2") (pintype "passive"))
      (node (ref "U3") (pin "4") (pinfunction "Y2_4") (pintype "power_in"))
    )
    (net (code "50") (name "/G5.1.F") (class "Default")
      (node (ref "Q29") (pin "2") (pinfunction "G_2") (pintype "passive"))
      (node (ref "R29") (pin "2") (pinfunction "2_2") (pintype "passive"))
      (node (ref "U3") (pin "2") (pinfunction "Y1_2") (pintype "power_in"))
    )
    (net (code "51") (name "/G5.2.E") (class "Default")
      (node (ref "Q32") (pin "2") (pinfunction "G_2") (pintype "passive"))
      (node (ref "R32") (pin "2") (pinfunction "2_2") (pintype "passive"))
      (node (ref "U3") (pin "12") (pinfunction "Y6_12") (pintype "power_in"))
    )
    (net (code "52") (name "/G5.2.F") (class "Default")
      (node (ref "Q31") (pin "2") (pinfunction "G_2") (pintype "passive"))
      (node (ref "R31") (pin "2") (pinfunction "2_2") (pintype "passive"))
      (node (ref "U3") (pin "6") (pinfunction "Y3_6") (pintype "power_in"))
    )
    (net (code "53") (name "/G5.3.E") (class "Default")
      (node (ref "Q34") (pin "2") (pinfunction "G_2") (pintype "passive"))
    )
    (net (code "54") (name "/G5.3.E.1") (class "Default")
      (node (ref "R34") (pin "2") (pinfunction "2_2") (pintype "passive"))
      (node (ref "U3") (pin "8") (pinfunction "Y4_8") (pintype "power_in"))
    )
    (net (code "55") (name "/G5.3.F") (class "Default")
      (node (ref "Q33") (pin "2") (pinfunction "G_2") (pintype "passive"))
    )
    (net (code "56") (name "/G5.3.F.1") (class "Default")
      (node (ref "R33") (pin "2") (pinfunction "2_2") (pintype "passive"))
      (node (ref "U3") (pin "10") (pinfunction "Y5_10") (pintype "power_in"))
    )
    (net (code "57") (name "/G5.AB") (class "Default")
      (node (ref "Q27") (pin "2") (pinfunction "G_2") (pintype "passive"))
      (node (ref "R39") (pin "2") (pinfunction "2_2") (pintype "passive"))
      (node (ref "U4") (pin "12") (pinfunction "Y6_12") (pintype "power_in"))
    )
    (net (code "58") (name "/G5.AD") (class "Default")
      (node (ref "Q28") (pin "2") (pinfunction "G_2") (pintype "passive"))
      (node (ref "R40") (pin "2") (pinfunction "2_2") (pintype "passive"))
      (node (ref "U4") (pin "10") (pinfunction "Y5_10") (pintype "power_in"))
    )
    (net (code "59") (name "/O1.1.E") (class "Default")
      (node (ref "U1") (pin "3") (pinfunction "A2_3") (pintype "power_in"))
    )
    (net (code "60") (name "/O1.1.F") (class "Default")
      (node (ref "U1") (pin "1") (pinfunction "A1_1") (pintype "power_in"))
    )
    (net (code "61") (name "/O1.2.E") (class "Default")
      (node (ref "U1") (pin "15") (pinfunction "A6_15") (pintype "power_in"))
    )
    (net (code "62") (name "/O1.2.F") (class "Default")
      (node (ref "U1") (pin "5") (pinfunction "A3_5") (pintype "power_in"))
    )
    (net (code "63") (name "/O1.3.E") (class "Default")
      (node (ref "U1") (pin "9") (pinfunction "A4_9") (pintype "power_in"))
    )
    (net (code "64") (name "/O1.3.F") (class "Default")
      (node (ref "U1") (pin "11") (pinfunction "A5_11") (pintype "power_in"))
    )
    (net (code "65") (name "/O1.AB") (class "Default")
      (node (ref "U4") (pin "1") (pinfunction "A1_1") (pintype "power_in"))
    )
    (net (code "66") (name "/O1.AD") (class "Default")
      (node (ref "U4") (pin "3") (pinfunction "A2_3") (pintype "power_in"))
    )
    (net (code "67") (name "/O3.1.E") (class "Default")
      (node (ref "U2") (pin "3") (pinfunction "A2_3") (pintype "power_in"))
    )
    (net (code "68") (name "/O3.1.F") (class "Default")
      (node (ref "U2") (pin "1") (pinfunction "A1_1") (pintype "power_in"))
    )
    (net (code "69") (name "/O3.2.E") (class "Default")
      (node (ref "Q20") (pin "2") (pinfunction "G_2") (pintype "passive"))
      (node (ref "U2") (pin "15") (pinfunction "A6_15") (pintype "power_in"))
    )
    (net (code "70") (name "/O3.2.F") (class "Default")
      (node (ref "Q19") (pin "2") (pinfunction "G_2") (pintype "passive"))
    )
    (net (code "71") (name "/O3.3.E") (class "Default")
      (node (ref "U2") (pin "9") (pinfunction "A4_9") (pintype "power_in"))
    )
    (net (code "72") (name "/O3.3.F") (class "Default")
      (node (ref "U2") (pin "11") (pinfunction "A5_11") (pintype "power_in"))
    )
    (net (code "73") (name "/O5.1.E") (class "Default")
      (node (ref "U3") (pin "3") (pinfunction "A2_3") (pintype "power_in"))
    )
    (net (code "74") (name "/O5.1.F") (class "Default")
      (node (ref "U3") (pin "1") (pinfunction "A1_1") (pintype "power_in"))
    )
    (net (code "75") (name "/O5.2.E") (class "Default")
      (node (ref "U3") (pin "15") (pinfunction "A6_15") (pintype "power_in"))
    )
    (net (code "76") (name "/O5.2.F") (class "Default")
      (node (ref "U3") (pin "5") (pinfunction "A3_5") (pintype "power_in"))
    )
    (net (code "77") (name "/O5.3.E") (class "Default")
      (node (ref "U3") (pin "9") (pinfunction "A4_9") (pintype "power_in"))
    )
    (net (code "78") (name "/O5.3.F") (class "Default")
      (node (ref "U3") (pin "11") (pinfunction "A5_11") (pintype "power_in"))
    )
    (net (code "79") (name "/O5.AB") (class "Default")
      (node (ref "U4") (pin "15") (pinfunction "A6_15") (pintype "power_in"))
    )
    (net (code "80") (name "/O5.AD") (class "Default")
      (node (ref "U4") (pin "11") (pinfunction "A5_11") (pintype "power_in"))
    )
    (net (code "81") (name "3.3VD") (class "Default")
      (node (ref "U1") (pin "14") (pinfunction "Vcc_14") (pintype "power_in"))
      (node (ref "U2") (pin "14") (pinfunction "Vcc_14") (pintype "power_in"))
      (node (ref "U3") (pin "14") (pinfunction "Vcc_14") (pintype "power_in"))
      (node (ref "U4") (pin "14") (pinfunction "Vcc_14") (pintype "power_in"))
    )
    (net (code "82") (name "GND") (class "Default")
      (node (ref "Q1") (pin "3") (pinfunction "S_3") (pintype "passive"))
      (node (ref "Q10") (pin "3") (pinfunction "S_3") (pintype "passive"))
      (node (ref "Q11") (pin "3") (pinfunction "S_3") (pintype "passive"))
      (node (ref "Q12") (pin "3") (pinfunction "S_3") (pintype "passive"))
      (node (ref "Q13") (pin "3") (pinfunction "S_3") (pintype "passive"))
      (node (ref "Q14") (pin "3") (pinfunction "S_3") (pintype "passive"))
      (node (ref "Q15") (pin "3") (pinfunction "S_3") (pintype "passive"))
      (node (ref "Q16") (pin "3") (pinfunction "S_3") (pintype "passive"))
      (node (ref "Q17") (pin "3") (pinfunction "S_3") (pintype "passive"))
      (node (ref "Q18") (pin "3") (pinfunction "S_3") (pintype "passive"))
      (node (ref "Q19") (pin "3") (pinfunction "S_3") (pintype "passive"))
      (node (ref "Q2") (pin "3") (pinfunction "S_3") (pintype "passive"))
      (node (ref "Q20") (pin "3") (pinfunction "S_3") (pintype "passive"))
      (node (ref "Q21") (pin "3") (pinfunction "S_3") (pintype "passive"))
      (node (ref "Q22") (pin "3") (pinfunction "S_3") (pintype "passive"))
      (node (ref "Q23") (pin "3") (pinfunction "S_3") (pintype "passive"))
      (node (ref "Q24") (pin "3") (pinfunction "S_3") (pintype "passive"))
      (node (ref "Q25") (pin "3") (pinfunction "S_3") (pintype "passive"))
      (node (ref "Q26") (pin "3") (pinfunction "S_3") (pintype "passive"))
      (node (ref "Q27") (pin "3") (pinfunction "S_3") (pintype "passive"))
      (node (ref "Q28") (pin "3") (pinfunction "S_3") (pintype "passive"))
      (node (ref "Q29") (pin "3") (pinfunction "S_3") (pintype "passive"))
      (node (ref "Q3") (pin "3") (pinfunction "S_3") (pintype "passive"))
      (node (ref "Q30") (pin "3") (pinfunction "S_3") (pintype "passive"))
      (node (ref "Q31") (pin "3") (pinfunction "S_3") (pintype "passive"))
      (node (ref "Q32") (pin "3") (pinfunction "S_3") (pintype "passive"))
      (node (ref "Q33") (pin "3") (pinfunction "S_3") (pintype "passive"))
      (node (ref "Q34") (pin "3") (pinfunction "S_3") (pintype "passive"))
      (node (ref "Q4") (pin "3") (pinfunction "S_3") (pintype "passive"))
      (node (ref "Q5") (pin "3") (pinfunction "S_3") (pintype "passive"))
      (node (ref "Q6") (pin "3") (pinfunction "S_3") (pintype "passive"))
      (node (ref "Q7") (pin "3") (pinfunction "S_3") (pintype "passive"))
      (node (ref "Q8") (pin "3") (pinfunction "S_3") (pintype "passive"))
      (node (ref "Q9") (pin "3") (pinfunction "S_3") (pintype "passive"))
      (node (ref "R10") (pin "1") (pinfunction "1_1") (pintype "passive"))
      (node (ref "R11") (pin "1") (pinfunction "1_1") (pintype "passive"))
      (node (ref "R12") (pin "1") (pinfunction "1_1") (pintype "passive"))
      (node (ref "R13") (pin "1") (pinfunction "1_1") (pintype "passive"))
      (node (ref "R14") (pin "1") (pinfunction "1_1") (pintype "passive"))
      (node (ref "R15") (pin "1") (pinfunction "1_1") (pintype "passive"))
      (node (ref "R16") (pin "1") (pinfunction "1_1") (pintype "passive"))
      (node (ref "R17") (pin "1") (pinfunction "1_1") (pintype "passive"))
      (node (ref "R18") (pin "1") (pinfunction "1_1") (pintype "passive"))
      (node (ref "R19") (pin "1") (pinfunction "1_1") (pintype "passive"))
      (node (ref "R20") (pin "1") (pinfunction "1_1") (pintype "passive"))
      (node (ref "R21") (pin "1") (pinfunction "1_1") (pintype "passive"))
      (node (ref "R22") (pin "1") (pinfunction "1_1") (pintype "passive"))
      (node (ref "R23") (pin "1") (pinfunction "1_1") (pintype "passive"))
      (node (ref "R24") (pin "1") (pinfunction "1_1") (pintype "passive"))
      (node (ref "R25") (pin "1") (pinfunction "1_1") (pintype "passive"))
      (node (ref "R26") (pin "1") (pinfunction "1_1") (pintype "passive"))
      (node (ref "R27") (pin "1") (pinfunction "1_1") (pintype "passive"))
      (node (ref "R28") (pin "1") (pinfunction "1_1") (pintype "passive"))
      (node (ref "R29") (pin "1") (pinfunction "1_1") (pintype "passive"))
      (node (ref "R30") (pin "1") (pinfunction "1_1") (pintype "passive"))
      (node (ref "R31") (pin "1") (pinfunction "1_1") (pintype "passive"))
      (node (ref "R32") (pin "1") (pinfunction "1_1") (pintype "passive"))
      (node (ref "R33") (pin "1") (pinfunction "1_1") (pintype "passive"))
      (node (ref "R34") (pin "1") (pinfunction "1_1") (pintype "passive"))
      (node (ref "R35") (pin "1") (pinfunction "1_1") (pintype "passive"))
      (node (ref "R36") (pin "1") (pinfunction "1_1") (pintype "passive"))
      (node (ref "R37") (pin "1") (pinfunction "1_1") (pintype "passive"))
      (node (ref "R38") (pin "1") (pinfunction "1_1") (pintype "passive"))
      (node (ref "R39") (pin "1") (pinfunction "1_1") (pintype "passive"))
      (node (ref "R40") (pin "1") (pinfunction "1_1") (pintype "passive"))
      (node (ref "R7") (pin "1") (pinfunction "1_1") (pintype "passive"))
      (node (ref "R8") (pin "1") (pinfunction "1_1") (pintype "passive"))
      (node (ref "R9") (pin "1") (pinfunction "1_1") (pintype "passive"))
      (node (ref "U1") (pin "7") (pinfunction "GND_7") (pintype "passive"))
      (node (ref "U2") (pin "7") (pinfunction "GND_7") (pintype "passive"))
      (node (ref "U3") (pin "7") (pinfunction "GND_7") (pintype "passive"))
      (node (ref "U4") (pin "5") (pinfunction "A3_5") (pintype "power_in"))
      (node (ref "U4") (pin "6") (pinfunction "Y3_6") (pintype "power_in"))
      (node (ref "U4") (pin "7") (pinfunction "GND_7") (pintype "passive"))
      (node (ref "U4") (pin "8") (pinfunction "Y4_8") (pintype "power_in"))
      (node (ref "U4") (pin "9") (pinfunction "A4_9") (pintype "power_in"))
    )
    (net (code "83") (name "Net-(D2-K)") (class "Default")
      (node (ref "D2") (pin "2") (pinfunction "K_2") (pintype "passive"))
      (node (ref "Q1") (pin "1") (pinfunction "D_1") (pintype "passive"))
    )
    (net (code "84") (name "Net-(D3-K)") (class "Default")
      (node (ref "D3") (pin "2") (pinfunction "K_2") (pintype "passive"))
      (node (ref "Q2") (pin "1") (pinfunction "D_1") (pintype "passive"))
    )
    (net (code "85") (name "Net-(D4-K)") (class "Default")
      (node (ref "D4") (pin "2") (pinfunction "K_2") (pintype "passive"))
      (node (ref "Q3") (pin "1") (pinfunction "D_1") (pintype "passive"))
    )
    (net (code "86") (name "Net-(D5-K)") (class "Default")
      (node (ref "D5") (pin "2") (pinfunction "K_2") (pintype "passive"))
      (node (ref "Q4") (pin "1") (pinfunction "D_1") (pintype "passive"))
    )
    (net (code "87") (name "Net-(D6-K)") (class "Default")
      (node (ref "D6") (pin "2") (pinfunction "K_2") (pintype "passive"))
      (node (ref "Q5") (pin "1") (pinfunction "D_1") (pintype "passive"))
    )
    (net (code "88") (name "Net-(D7-K)") (class "Default")
      (node (ref "D7") (pin "2") (pinfunction "K_2") (pintype "passive"))
      (node (ref "Q6") (pin "1") (pinfunction "D_1") (pintype "passive"))
    )
    (net (code "89") (name "Net-(D8-K)") (class "Default")
      (node (ref "D8") (pin "2") (pinfunction "K_2") (pintype "passive"))
      (node (ref "Q7") (pin "1") (pinfunction "D_1") (pintype "passive"))
    )
    (net (code "90") (name "Net-(D9-K)") (class "Default")
      (node (ref "D9") (pin "2") (pinfunction "K_2") (pintype "passive"))
      (node (ref "Q8") (pin "1") (pinfunction "D_1") (pintype "passive"))
    )
    (net (code "91") (name "Net-(D10-K)") (class "Default")
      (node (ref "D10") (pin "2") (pinfunction "K_2") (pintype "passive"))
      (node (ref "Q9") (pin "1") (pinfunction "D_1") (pintype "passive"))
    )
    (net (code "92") (name "Net-(D11-K)") (class "Default")
      (node (ref "D11") (pin "2") (pinfunction "K_2") (pintype "passive"))
      (node (ref "Q10") (pin "1") (pinfunction "D_1") (pintype "passive"))
    )
    (net (code "93") (name "Net-(D12-K)") (class "Default")
      (node (ref "D12") (pin "2") (pinfunction "K_2") (pintype "passive"))
      (node (ref "Q11") (pin "1") (pinfunction "D_1") (pintype "passive"))
    )
    (net (code "94") (name "Net-(D13-K)") (class "Default")
      (node (ref "D13") (pin "2") (pinfunction "K_2") (pintype "passive"))
      (node (ref "Q12") (pin "1") (pinfunction "D_1") (pintype "passive"))
    )
    (net (code "95") (name "Net-(D14-K)") (class "Default")
      (node (ref "D14") (pin "2") (pinfunction "K_2") (pintype "passive"))
      (node (ref "Q13") (pin "1") (pinfunction "D_1") (pintype "passive"))
    )
    (net (code "96") (name "Net-(D15-K)") (class "Default")
      (node (ref "D15") (pin "2") (pinfunction "K_2") (pintype "passive"))
      (node (ref "Q14") (pin "1") (pinfunction "D_1") (pintype "passive"))
    )
    (net (code "97") (name "Net-(D16-K)") (class "Default")
      (node (ref "D16") (pin "2") (pinfunction "K_2") (pintype "passive"))
      (node (ref "Q15") (pin "1") (pinfunction "D_1") (pintype "passive"))
    )
    (net (code "98") (name "Net-(D17-K)") (class "Default")
      (node (ref "D17") (pin "2") (pinfunction "K_2") (pintype "passive"))
      (node (ref "Q16") (pin "1") (pinfunction "D_1") (pintype "passive"))
    )
    (net (code "99") (name "Net-(D18-K)") (class "Default")
      (node (ref "D18") (pin "2") (pinfunction "K_2") (pintype "passive"))
      (node (ref "Q17") (pin "1") (pinfunction "D_1") (pintype "passive"))
    )
    (net (code "100") (name "Net-(D19-K)") (class "Default")
      (node (ref "D19") (pin "2") (pinfunction "K_2") (pintype "passive"))
      (node (ref "Q18") (pin "1") (pinfunction "D_1") (pintype "passive"))
    )
    (net (code "101") (name "Net-(D20-K)") (class "Default")
      (node (ref "D20") (pin "2") (pinfunction "K_2") (pintype "passive"))
      (node (ref "Q19") (pin "1") (pinfunction "D_1") (pintype "passive"))
    )
    (net (code "102") (name "Net-(D21-K)") (class "Default")
      (node (ref "D21") (pin "2") (pinfunction "K_2") (pintype "passive"))
      (node (ref "Q20") (pin "1") (pinfunction "D_1") (pintype "passive"))
    )
    (net (code "103") (name "Net-(D22-K)") (class "Default")
      (node (ref "D22") (pin "2") (pinfunction "K_2") (pintype "passive"))
      (node (ref "Q21") (pin "1") (pinfunction "D_1") (pintype "passive"))
    )
    (net (code "104") (name "Net-(D23-K)") (class "Default")
      (node (ref "D23") (pin "2") (pinfunction "K_2") (pintype "passive"))
      (node (ref "Q22") (pin "1") (pinfunction "D_1") (pintype "passive"))
    )
    (net (code "105") (name "Net-(D24-K)") (class "Default")
      (node (ref "D24") (pin "2") (pinfunction "K_2") (pintype "passive"))
      (node (ref "Q23") (pin "1") (pinfunction "D_1") (pintype "passive"))
    )
    (net (code "106") (name "Net-(D25-K)") (class "Default")
      (node (ref "D25") (pin "2") (pinfunction "K_2") (pintype "passive"))
      (node (ref "Q24") (pin "1") (pinfunction "D_1") (pintype "passive"))
    )
    (net (code "107") (name "Net-(D26-K)") (class "Default")
      (node (ref "D26") (pin "2") (pinfunction "K_2") (pintype "passive"))
      (node (ref "Q25") (pin "1") (pinfunction "D_1") (pintype "passive"))
    )
    (net (code "108") (name "Net-(D27-K)") (class "Default")
      (node (ref "D27") (pin "2") (pinfunction "K_2") (pintype "passive"))
      (node (ref "Q26") (pin "1") (pinfunction "D_1") (pintype "passive"))
    )
    (net (code "109") (name "Net-(D28-K)") (class "Default")
      (node (ref "D28") (pin "2") (pinfunction "K_2") (pintype "passive"))
      (node (ref "Q27") (pin "1") (pinfunction "D_1") (pintype "passive"))
    )
    (net (code "110") (name "Net-(D29-K)") (class "Default")
      (node (ref "D29") (pin "2") (pinfunction "K_2") (pintype "passive"))
      (node (ref "Q28") (pin "1") (pinfunction "D_1") (pintype "passive"))
    )
    (net (code "111") (name "Net-(D30-K)") (class "Default")
      (node (ref "D30") (pin "2") (pinfunction "K_2") (pintype "passive"))
      (node (ref "Q29") (pin "1") (pinfunction "D_1") (pintype "passive"))
    )
    (net (code "112") (name "Net-(D31-K)") (class "Default")
      (node (ref "D31") (pin "2") (pinfunction "K_2") (pintype "passive"))
      (node (ref "Q30") (pin "1") (pinfunction "D_1") (pintype "passive"))
    )
    (net (code "113") (name "Net-(D32-K)") (class "Default")
      (node (ref "D32") (pin "2") (pinfunction "K_2") (pintype "passive"))
      (node (ref "Q31") (pin "1") (pinfunction "D_1") (pintype "passive"))
    )
    (net (code "114") (name "Net-(D33-K)") (class "Default")
      (node (ref "D33") (pin "2") (pinfunction "K_2") (pintype "passive"))
      (node (ref "Q32") (pin "1") (pinfunction "D_1") (pintype "passive"))
    )
    (net (code "115") (name "Net-(D34-K)") (class "Default")
      (node (ref "D34") (pin "2") (pinfunction "K_2") (pintype "passive"))
      (node (ref "Q33") (pin "1") (pinfunction "D_1") (pintype "passive"))
    )
    (net (code "116") (name "Net-(D35-K)") (class "Default")
      (node (ref "D35") (pin "2") (pinfunction "K_2") (pintype "passive"))
      (node (ref "Q34") (pin "1") (pinfunction "D_1") (pintype "passive"))
    )
    (net (code "117") (name "unconnected-(U2-Y3-Pad6)") (class "Default")
      (node (ref "U2") (pin "6") (pinfunction "Y3_6") (pintype "power_in"))
    )
  )
)
